# lpf_160.net
KiCad netlist of a schematic drawn in Altium Designer
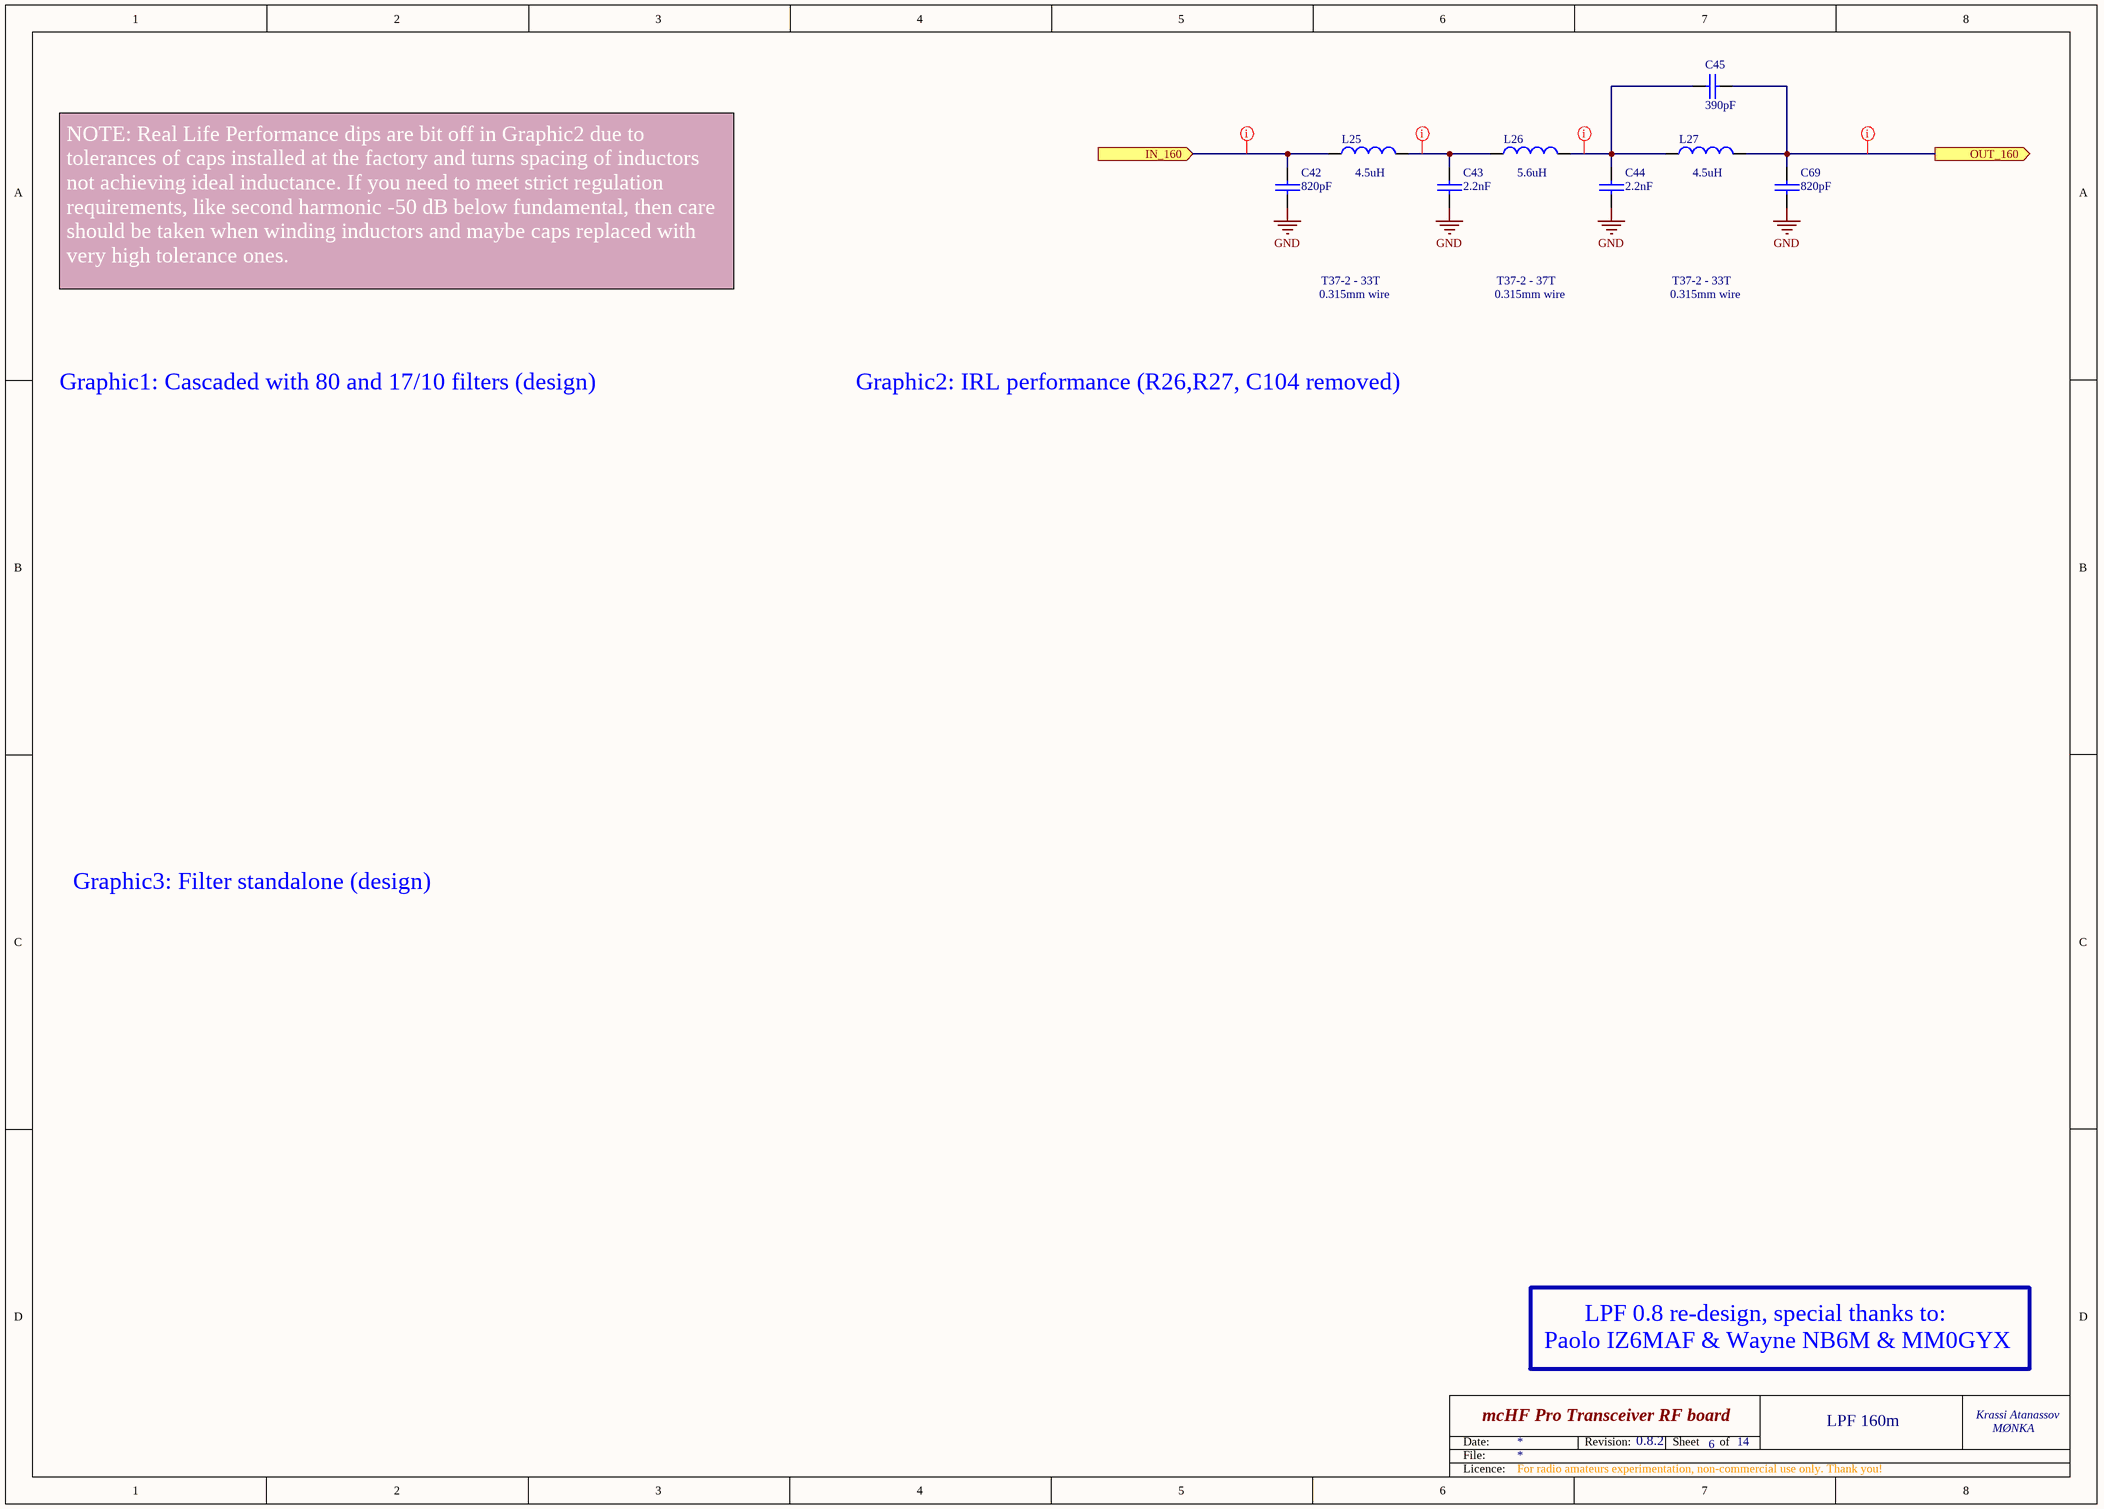
[diagram p0: lpf_160.SchDoc]

(export (version "E")
  (design (tool "Eeschema 10.0.6"))
  (components
    (comp (ref "C42")
      (value "820pF")
      (footprint "0805")
      (description "Capacitor")
      (fields (field (name "VOLTAGE") "100V"))
      (libsource (lib "mcHF_rf") (part "CAP"))
    )
    (comp (ref "C43")
      (value "2.2nF")
      (footprint "0805")
      (description "Capacitor")
      (fields (field (name "VOLTAGE") "100V"))
      (libsource (lib "mcHF_rf") (part "CAP"))
    )
    (comp (ref "C44")
      (value "2.2nF")
      (footprint "0805")
      (description "Capacitor")
      (fields (field (name "VOLTAGE") "100V"))
      (libsource (lib "mcHF_rf") (part "CAP"))
    )
    (comp (ref "C45")
      (value "390pF")
      (footprint "0805")
      (description "Capacitor")
      (fields (field (name "VOLTAGE") "100V"))
      (libsource (lib "mcHF_rf") (part "CAP"))
    )
    (comp (ref "C69")
      (value "820pF")
      (footprint "0805")
      (description "Capacitor")
      (fields (field (name "VOLTAGE") "100V"))
      (libsource (lib "mcHF_rf") (part "CAP"))
    )
    (comp (ref "L25")
      (value "T37-2")
      (footprint "LPF_IND")
      (description "T37-2 handwound inductor")
      (fields (field (name "INDUCTANCE") "4.5uH"))
      (libsource (lib "mcHF_rf") (part "LPF_IND"))
    )
    (comp (ref "L26")
      (value "T37-2")
      (footprint "LPF_IND")
      (description "T37-2 handwound inductor")
      (fields (field (name "INDUCTANCE") "5.6uH"))
      (libsource (lib "mcHF_rf") (part "LPF_IND"))
    )
    (comp (ref "L27")
      (value "T37-2")
      (footprint "LPF_IND")
      (description "T37-2 handwound inductor")
      (fields (field (name "INDUCTANCE") "4.5uH"))
      (libsource (lib "mcHF_rf") (part "LPF_IND"))
    )
  )
  (nets
    (net (code "1") (name "/IN_160") (class "Default")
      (node (ref "C42") (pin "1") (pinfunction "1_1") (pintype "passive"))
      (node (ref "L25") (pin "1") (pinfunction "1_1") (pintype "passive"))
    )
    (net (code "2") (name "/OUT_160") (class "Default")
      (node (ref "C45") (pin "1") (pinfunction "1_1") (pintype "passive"))
      (node (ref "C69") (pin "1") (pinfunction "1_1") (pintype "passive"))
      (node (ref "L27") (pin "2") (pinfunction "2_2") (pintype "passive"))
    )
    (net (code "3") (name "GND") (class "Default")
      (node (ref "C42") (pin "2") (pinfunction "2_2") (pintype "passive"))
      (node (ref "C43") (pin "2") (pinfunction "2_2") (pintype "passive"))
      (node (ref "C44") (pin "2") (pinfunction "2_2") (pintype "passive"))
      (node (ref "C69") (pin "2") (pinfunction "2_2") (pintype "passive"))
    )
    (net (code "4") (name "Net-(C43-Pad1)") (class "Default")
      (node (ref "C43") (pin "1") (pinfunction "1_1") (pintype "passive"))
      (node (ref "L25") (pin "2") (pinfunction "2_2") (pintype "passive"))
      (node (ref "L26") (pin "1") (pinfunction "1_1") (pintype "passive"))
    )
    (net (code "5") (name "Net-(C44-Pad1)") (class "Default")
      (node (ref "C44") (pin "1") (pinfunction "1_1") (pintype "passive"))
      (node (ref "C45") (pin "2") (pinfunction "2_2") (pintype "passive"))
      (node (ref "L26") (pin "2") (pinfunction "2_2") (pintype "passive"))
      (node (ref "L27") (pin "1") (pinfunction "1_1") (pintype "passive"))
    )
  )
)
